# Main.net
KiCad netlist of a schematic drawn in Altium Designer
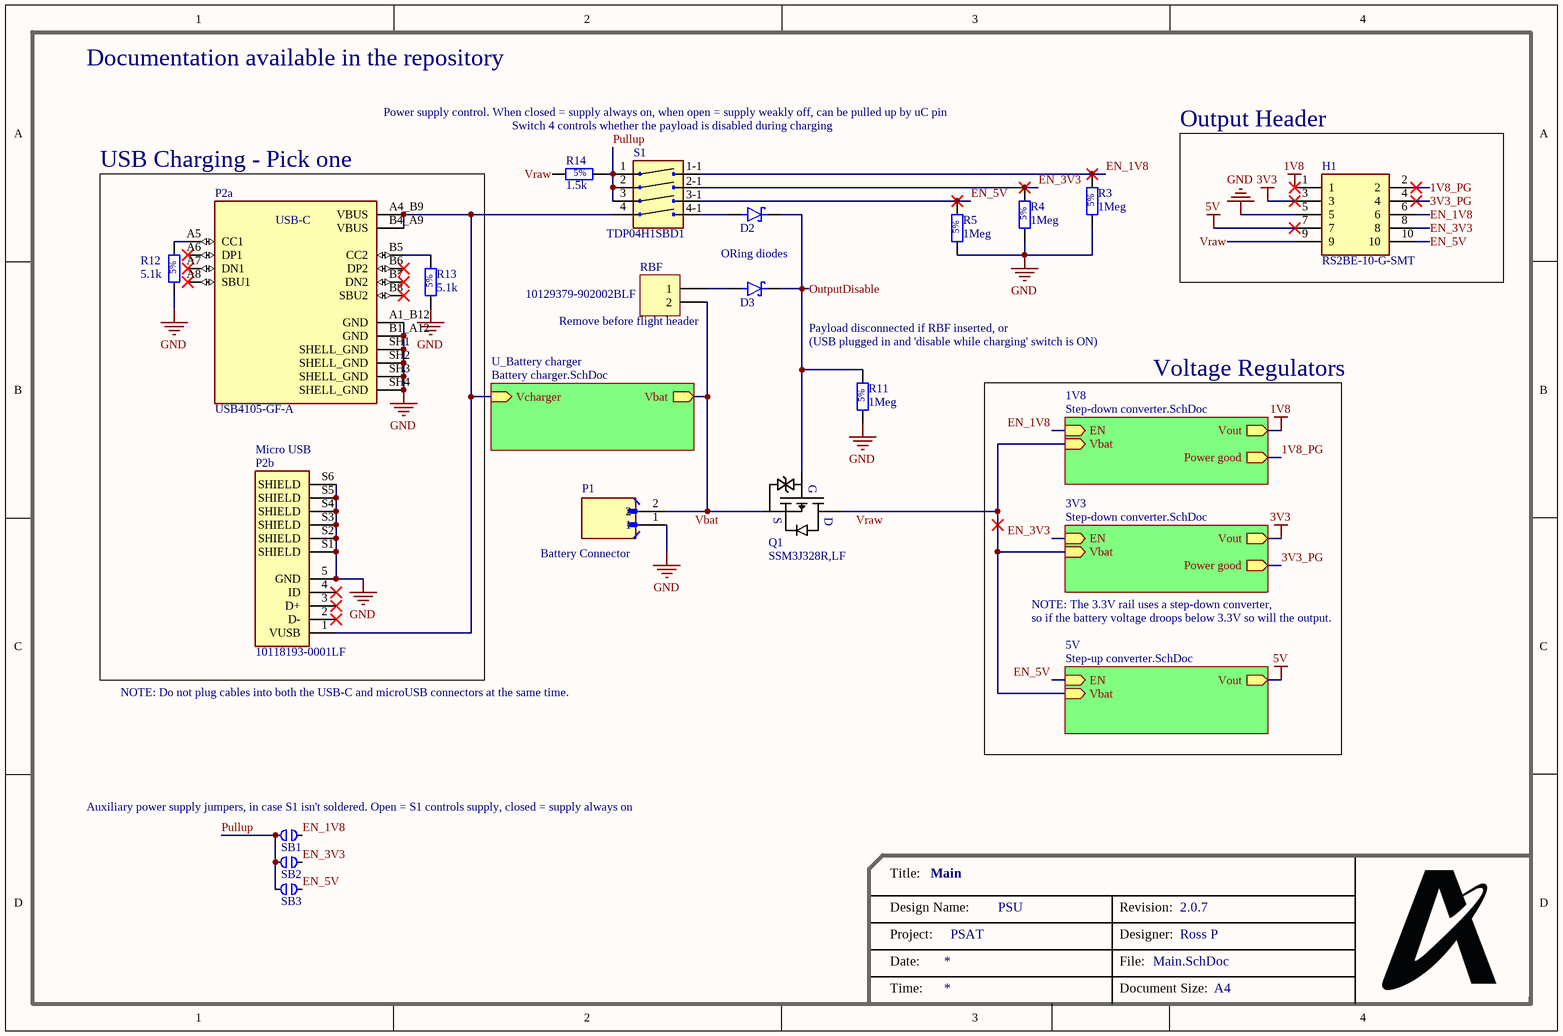
[diagram p0: Main.SchDoc]

(export (version "E")
  (design (tool "Eeschema 10.0.6"))
  (components
    (comp (ref "D2")
      (value "SS0520_R1_00001")
      (footprint "APSS Prototype Parts:SOD123-1.35mm-N")
      (description "Diode - Low Forward Voltage, Schottky, 385 mV @ 500 mA, 75 µA Reverse @ 10 V, SOD-123")
      (fields (field (name "APSS STANDARD PART") "APSS Standard"))
      (libsource (lib "APSS Prototype Parts") (part "SS0520_R1_00001"))
    )
    (comp (ref "D3")
      (value "SS0520_R1_00001")
      (footprint "APSS Prototype Parts:SOD123-1.35mm-N")
      (description "Diode - Low Forward Voltage, Schottky, 385 mV @ 500 mA, 75 µA Reverse @ 10 V, SOD-123")
      (fields (field (name "APSS STANDARD PART") "APSS Standard"))
      (libsource (lib "APSS Prototype Parts") (part "SS0520_R1_00001"))
    )
    (comp (ref "H1")
      (value "RS2BE-10-G-SMT")
      (footprint "RS2BE10GSMT")
      (description "Receptacle Strip 10P 2.54mm Pitch SMT")
      (libsource (lib "RS2BE-10-G-SMT") (part "RS2BE-10-G-SMT"))
    )
    (comp (ref "P1")
      (value "B2B-PH-K-S(LF)(SN)")
      (footprint "JST_B2B-PH-K-S(LF)(SN)")
      (description "Connector Header Through Hole 2 position 0.079 (2.00mm)")
      (fields (field (name "MF PART NO.") "B2B-PH-K-S (LF)(SN)"))
      (libsource (lib "B2B-PH-K-S_LF__SN_") (part "B2B-PH-K-S(LF)(SN)"))
    )
    (comp (ref "P2a")
      (value "USB4105-GF-A")
      (footprint "GCT_USB4105-GF-A")
      (libsource (lib "USB4105-GF-A") (part "USB4105-GF-A"))
    )
    (comp (ref "P2b")
      (value "10118193-0001LF")
      (footprint "AMPHENOL_10118193-0001LF")
      (description "Micro USB 2.0, Input Output Connectors, B TYPE RECEPTACLE")
      (fields (field (name "MF") "Amphenol ICC"))
      (libsource (lib "10118193-0001LF") (part "10118193-0001LF"))
    )
    (comp (ref "Q1")
      (value "SSM3J328R,LF")
      (footprint "APSS Prototype Parts:SOT23F-3-0.8mm")
      (description "Transistor - MOSFET, P-Channel SSM3J328R,LF")
      (fields (field (name "POWER") "1W") (field (name "APSS STANDARD PART") "APSS Standard"))
      (libsource (lib "APSS Prototype Parts") (part "SSM3J328R,LF"))
    )
    (comp (ref "R3")
      (value "1Meg")
      (footprint "APSS Flight Parts:Resistor_0805_2012M-50N")
      (fields
        (field (name "TOLERANCE") "5%")
        (field (name "POWER") "1/8W")
        (field (name "MF PART NO.") "RMCF0805JT1M00")
      )
      (libsource (lib "APSS Prototype Parts") (part "RMCF0805JT Series"))
    )
    (comp (ref "R4")
      (value "1Meg")
      (footprint "APSS Flight Parts:Resistor_0805_2012M-50N")
      (fields
        (field (name "TOLERANCE") "5%")
        (field (name "POWER") "1/8W")
        (field (name "MF PART NO.") "RMCF0805JT1M00")
      )
      (libsource (lib "APSS Prototype Parts") (part "RMCF0805JT Series"))
    )
    (comp (ref "R5")
      (value "1Meg")
      (footprint "APSS Flight Parts:Resistor_0805_2012M-50N")
      (fields
        (field (name "TOLERANCE") "5%")
        (field (name "POWER") "1/8W")
        (field (name "MF PART NO.") "RMCF0805JT1M00")
      )
      (libsource (lib "APSS Prototype Parts") (part "RMCF0805JT Series"))
    )
    (comp (ref "R11")
      (value "1Meg")
      (footprint "APSS Flight Parts:Resistor_0805_2012M-50N")
      (fields
        (field (name "TOLERANCE") "5%")
        (field (name "POWER") "1/8W")
        (field (name "MF PART NO.") "RMCF0805JT1M00")
      )
      (libsource (lib "APSS Prototype Parts") (part "RMCF0805JT Series"))
    )
    (comp (ref "R12")
      (value "5.1k")
      (footprint "APSS Flight Parts:Resistor_0805_2012M-50N")
      (fields
        (field (name "TOLERANCE") "5%")
        (field (name "POWER") "1/8W")
        (field (name "MF PART NO.") "RMCF0805JT5K10")
      )
      (libsource (lib "APSS Prototype Parts") (part "RMCF0805JT Series"))
    )
    (comp (ref "R13")
      (value "5.1k")
      (footprint "APSS Flight Parts:Resistor_0805_2012M-50N")
      (fields
        (field (name "TOLERANCE") "5%")
        (field (name "POWER") "1/8W")
        (field (name "MF PART NO.") "RMCF0805JT5K10")
      )
      (libsource (lib "APSS Prototype Parts") (part "RMCF0805JT Series"))
    )
    (comp (ref "R14")
      (value "1.5k")
      (footprint "APSS Flight Parts:Resistor_0805_2012M-50N")
      (fields
        (field (name "TOLERANCE") "5%")
        (field (name "POWER") "1/8W")
        (field (name "MF PART NO.") "RMCF0805JT1K50")
      )
      (libsource (lib "") (part "RMCF0805JT Series_1"))
    )
    (comp (ref "RBF")
      (value "~")
      (footprint "ECE-600102STTH-RA")
      (description "Short Before Flight")
      (libsource (lib "EceParts") (part "Header 2"))
    )
    (comp (ref "S1")
      (value "TDP04H1SBD1")
      (footprint "TDP04H1SBD1")
      (description "Switch")
      (libsource (lib "APSS Generic Components") (part "TDP04H1SBD1"))
    )
    (comp (ref "SB1")
      (value "Solder Jumper Normally Open 0201")
      (footprint "Solder Bridge Open 0201")
      (libsource (lib "APSS Generic Components") (part "Solder Jumper Normally Open 0201"))
    )
    (comp (ref "SB2")
      (value "Solder Jumper Normally Open 0201")
      (footprint "Solder Bridge Open 0201")
      (libsource (lib "APSS Generic Components") (part "Solder Jumper Normally Open 0201"))
    )
    (comp (ref "SB3")
      (value "Solder Jumper Normally Open 0201")
      (footprint "Solder Bridge Open 0201")
      (libsource (lib "APSS Generic Components") (part "Solder Jumper Normally Open 0201"))
    )
  )
  (nets
    (net (code "1") (name "/1V8_PG") (class "Default")
      (node (ref "H1") (pin "2") (pinfunction "2_2") (pintype "passive+no_connect"))
    )
    (net (code "2") (name "/3V3_PG") (class "Default")
      (node (ref "H1") (pin "4") (pinfunction "4_4") (pintype "passive+no_connect"))
    )
    (net (code "3") (name "/EN_1V8") (class "Default")
      (node (ref "H1") (pin "6") (pinfunction "6_6") (pintype "passive"))
      (node (ref "R3") (pin "2") (pinfunction "2_2") (pintype "passive"))
      (node (ref "S1") (pin "8") (pinfunction "1-1_8") (pintype "passive"))
      (node (ref "SB1") (pin "2") (pinfunction "2_2") (pintype "passive"))
    )
    (net (code "4") (name "/EN_3V3") (class "Default")
      (node (ref "H1") (pin "8") (pinfunction "8_8") (pintype "passive"))
      (node (ref "R4") (pin "2") (pinfunction "2_2") (pintype "passive"))
      (node (ref "S1") (pin "7") (pinfunction "2-1_7") (pintype "passive"))
      (node (ref "SB2") (pin "2") (pinfunction "2_2") (pintype "passive"))
    )
    (net (code "5") (name "/EN_5V") (class "Default")
      (node (ref "H1") (pin "10") (pinfunction "10_10") (pintype "passive"))
      (node (ref "R5") (pin "2") (pinfunction "2_2") (pintype "passive"))
      (node (ref "S1") (pin "6") (pinfunction "3-1_6") (pintype "passive"))
      (node (ref "SB3") (pin "2") (pinfunction "2_2") (pintype "passive"))
    )
    (net (code "6") (name "/OutputDisable") (class "Default")
      (node (ref "D2") (pin "C") (pinfunction "C_C") (pintype "passive"))
      (node (ref "D3") (pin "C") (pinfunction "C_C") (pintype "passive"))
      (node (ref "Q1") (pin "1") (pinfunction "G_1") (pintype "passive"))
      (node (ref "R11") (pin "2") (pinfunction "2_2") (pintype "passive"))
    )
    (net (code "7") (name "/Pullup") (class "Default")
      (node (ref "R14") (pin "2") (pinfunction "2_2") (pintype "passive"))
      (node (ref "S1") (pin "1") (pintype "passive"))
      (node (ref "S1") (pin "2") (pintype "passive"))
      (node (ref "S1") (pin "3") (pintype "passive"))
      (node (ref "SB1") (pin "1") (pinfunction "1_1") (pintype "passive"))
      (node (ref "SB2") (pin "1") (pinfunction "1_1") (pintype "passive"))
      (node (ref "SB3") (pin "1") (pinfunction "1_1") (pintype "passive"))
    )
    (net (code "8") (name "/Vbat") (class "Default")
      (node (ref "P1") (pin "2") (pinfunction "2_2") (pintype "passive"))
      (node (ref "Q1") (pin "2") (pinfunction "S_2") (pintype "passive"))
      (node (ref "RBF") (pin "2") (pinfunction "2_2") (pintype "passive"))
    )
    (net (code "9") (name "/Vcharger") (class "Default")
      (node (ref "P2a") (pin "A4_B9") (pinfunction "VBUS_A4_B9") (pintype "power_in"))
      (node (ref "P2a") (pin "B4_A9") (pinfunction "VBUS_B4_A9") (pintype "power_in"))
      (node (ref "P2b") (pin "1") (pinfunction "VUSB_1") (pintype "passive"))
      (node (ref "S1") (pin "4") (pintype "passive"))
    )
    (net (code "10") (name "/Vraw") (class "Default")
      (node (ref "H1") (pin "9") (pinfunction "9_9") (pintype "passive"))
      (node (ref "Q1") (pin "3") (pinfunction "D_3") (pintype "passive"))
      (node (ref "R14") (pin "1") (pinfunction "1_1") (pintype "passive"))
    )
    (net (code "11") (name "1V8") (class "Default")
      (node (ref "H1") (pin "1") (pinfunction "1_1") (pintype "passive"))
    )
    (net (code "12") (name "3V3") (class "Default")
      (node (ref "H1") (pin "3") (pinfunction "3_3") (pintype "passive"))
    )
    (net (code "13") (name "5V") (class "Default")
      (node (ref "H1") (pin "7") (pinfunction "7_7") (pintype "passive"))
    )
    (net (code "14") (name "GND") (class "Default")
      (node (ref "H1") (pin "5") (pinfunction "5_5") (pintype "passive"))
      (node (ref "P1") (pin "1") (pinfunction "1_1") (pintype "passive"))
      (node (ref "P2a") (pin "A1_B12") (pinfunction "GND_A1_B12") (pintype "power_in"))
      (node (ref "P2a") (pin "B1_A12") (pinfunction "GND_B1_A12") (pintype "power_in"))
      (node (ref "P2a") (pin "SH1") (pinfunction "SHELL_GND_SH1") (pintype "power_in"))
      (node (ref "P2a") (pin "SH2") (pinfunction "SHELL_GND_SH2") (pintype "power_in"))
      (node (ref "P2a") (pin "SH3") (pinfunction "SHELL_GND_SH3") (pintype "power_in"))
      (node (ref "P2a") (pin "SH4") (pinfunction "SHELL_GND_SH4") (pintype "power_in"))
      (node (ref "P2b") (pin "5") (pinfunction "GND_5") (pintype "passive"))
      (node (ref "P2b") (pin "S1") (pinfunction "SHIELD_S1") (pintype "passive"))
      (node (ref "P2b") (pin "S2") (pinfunction "SHIELD_S2") (pintype "passive"))
      (node (ref "P2b") (pin "S3") (pinfunction "SHIELD_S3") (pintype "passive"))
      (node (ref "P2b") (pin "S4") (pinfunction "SHIELD_S4") (pintype "passive"))
      (node (ref "P2b") (pin "S5") (pinfunction "SHIELD_S5") (pintype "passive"))
      (node (ref "P2b") (pin "S6") (pinfunction "SHIELD_S6") (pintype "passive"))
      (node (ref "R11") (pin "1") (pinfunction "1_1") (pintype "passive"))
      (node (ref "R12") (pin "1") (pinfunction "1_1") (pintype "passive"))
      (node (ref "R13") (pin "1") (pinfunction "1_1") (pintype "passive"))
      (node (ref "R3") (pin "1") (pinfunction "1_1") (pintype "passive"))
      (node (ref "R4") (pin "1") (pinfunction "1_1") (pintype "passive"))
      (node (ref "R5") (pin "1") (pinfunction "1_1") (pintype "passive"))
    )
    (net (code "15") (name "Net-(D3-PadA)") (class "Default")
      (node (ref "D3") (pin "A") (pinfunction "A_A") (pintype "passive"))
      (node (ref "RBF") (pin "1") (pinfunction "1_1") (pintype "passive"))
    )
    (net (code "16") (name "Net-(P2a-CC1)") (class "Default")
      (node (ref "P2a") (pin "A5") (pinfunction "CC1_A5") (pintype "bidirectional"))
      (node (ref "R12") (pin "2") (pinfunction "2_2") (pintype "passive"))
    )
    (net (code "17") (name "Net-(P2a-CC2)") (class "Default")
      (node (ref "P2a") (pin "B5") (pinfunction "CC2_B5") (pintype "bidirectional"))
      (node (ref "R13") (pin "2") (pinfunction "2_2") (pintype "passive"))
    )
    (net (code "18") (name "Net-(S1-4-1)") (class "Default")
      (node (ref "D2") (pin "A") (pinfunction "A_A") (pintype "passive"))
      (node (ref "S1") (pin "5") (pinfunction "4-1_5") (pintype "passive"))
    )
    (net (code "19") (name "unconnected-(P2a-DN1-PadA7)") (class "Default")
      (node (ref "P2a") (pin "A7") (pinfunction "DN1_A7") (pintype "bidirectional+no_connect"))
    )
    (net (code "20") (name "unconnected-(P2a-DN2-PadB7)") (class "Default")
      (node (ref "P2a") (pin "B7") (pinfunction "DN2_B7") (pintype "bidirectional+no_connect"))
    )
    (net (code "21") (name "unconnected-(P2a-DP1-PadA6)") (class "Default")
      (node (ref "P2a") (pin "A6") (pinfunction "DP1_A6") (pintype "bidirectional+no_connect"))
    )
    (net (code "22") (name "unconnected-(P2a-DP2-PadB6)") (class "Default")
      (node (ref "P2a") (pin "B6") (pinfunction "DP2_B6") (pintype "bidirectional+no_connect"))
    )
    (net (code "23") (name "unconnected-(P2a-SBU1-PadA8)") (class "Default")
      (node (ref "P2a") (pin "A8") (pinfunction "SBU1_A8") (pintype "bidirectional+no_connect"))
    )
    (net (code "24") (name "unconnected-(P2a-SBU2-PadB8)") (class "Default")
      (node (ref "P2a") (pin "B8") (pinfunction "SBU2_B8") (pintype "bidirectional+no_connect"))
    )
    (net (code "25") (name "unconnected-(P2b-D+-Pad3)") (class "Default")
      (node (ref "P2b") (pin "3") (pinfunction "D+_3") (pintype "passive+no_connect"))
    )
    (net (code "26") (name "unconnected-(P2b-D--Pad2)") (class "Default")
      (node (ref "P2b") (pin "2") (pinfunction "D-_2") (pintype "passive+no_connect"))
    )
    (net (code "27") (name "unconnected-(P2b-ID-Pad4)") (class "Default")
      (node (ref "P2b") (pin "4") (pinfunction "ID_4") (pintype "passive+no_connect"))
    )
  )
)
